# 20190608_ORIGAMI_V2-H-08slot-fixed.net
KiCad netlist of a schematic drawn in EAGLE
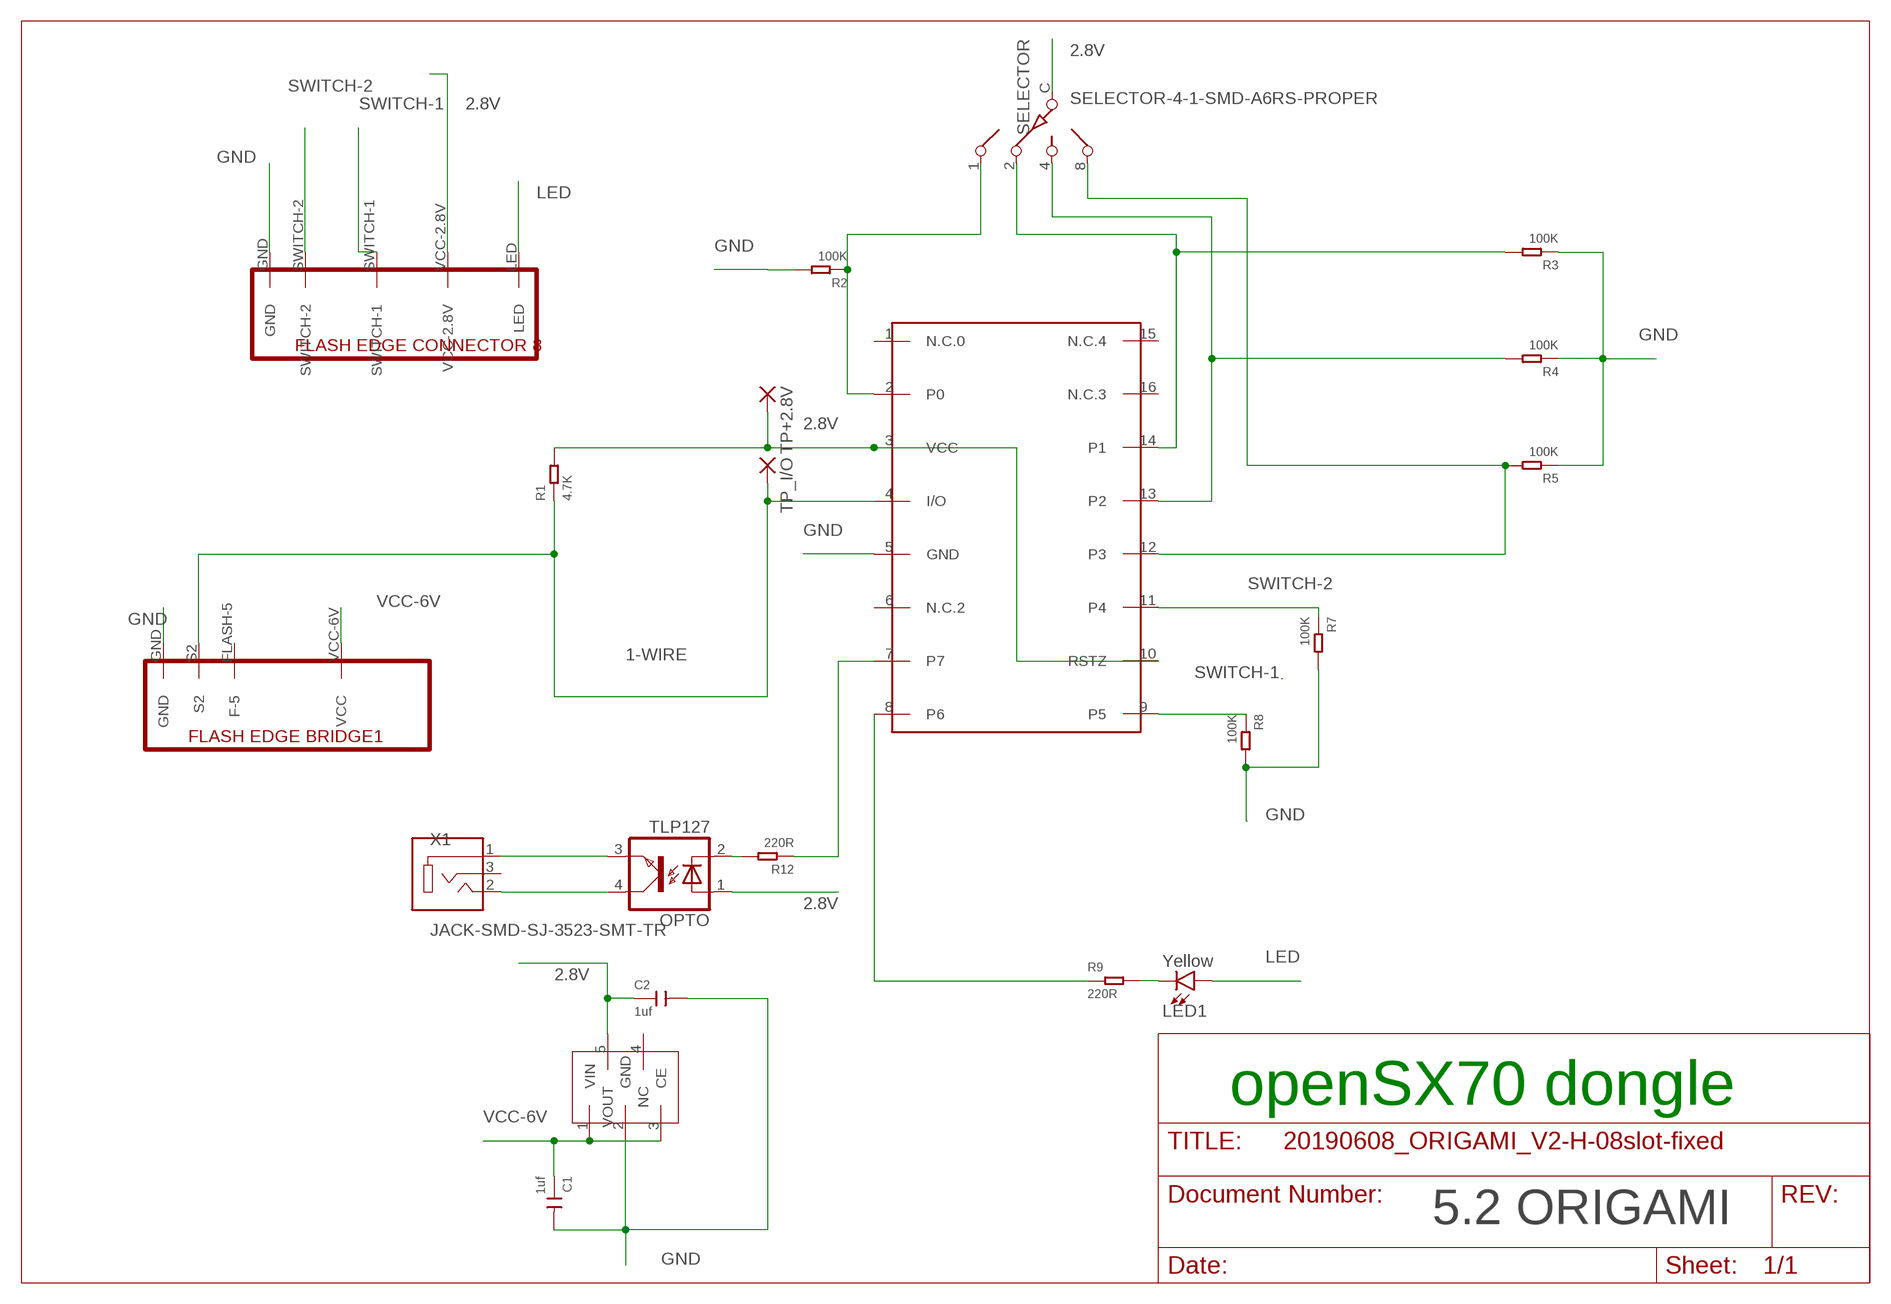
[diagram p0: schematic, sheet 1]

(export (version "E")
  (design (tool "Eeschema 10.0.6"))
  (components
    (comp (ref "C1")
      (value "1uf")
      (footprint "eagle-import:C0603")
      (fields (field (name "MPN") "CC0603KRX7R8BB105"))
      (libsource (lib "eagle-import") (part "CERAMIC-1UF-25V-10%-X7R(0603)"))
    )
    (comp (ref "C2")
      (value "1uf")
      (footprint "eagle-import:C0603")
      (fields (field (name "MPN") "CC0603KRX7R8BB105"))
      (libsource (lib "eagle-import") (part "CERAMIC-1UF-25V-10%-X7R(0603)"))
    )
    (comp (ref "DS2408")
      (value "DS2408")
      (footprint "eagle-import:SO16")
      (libsource (lib "eagle-import") (part "DS2408"))
    )
    (comp (ref "LED1")
      (value "Yellow")
      (footprint "eagle-import:LED-1206")
      (libsource (lib "eagle-import") (part "LED-YELLOWLILYPAD"))
    )
    (comp (ref "OPTO")
      (value "TLP127")
      (footprint "eagle-import:SO-4")
      (libsource (lib "eagle-import") (part "TLP127"))
    )
    (comp (ref "R1")
      (value "4.7K")
      (footprint "eagle-import:R0603")
      (fields (field (name "MPN") "RC0603JR-074K7L"))
      (libsource (lib "eagle-import") (part "SMD-RES-4.7K-5%-1/10W(0603)"))
    )
    (comp (ref "R2")
      (value "100K")
      (footprint "eagle-import:R0603")
      (fields (field (name "MPN") "RC0603FR-07100KL"))
      (libsource (lib "eagle-import") (part "SMD-RES-100K-1%-1/10W(0603)"))
    )
    (comp (ref "R3")
      (value "100K")
      (footprint "eagle-import:R0603")
      (fields (field (name "MPN") "RC0603FR-07100KL"))
      (libsource (lib "eagle-import") (part "SMD-RES-100K-1%-1/10W(0603)"))
    )
    (comp (ref "R4")
      (value "100K")
      (footprint "eagle-import:R0603")
      (fields (field (name "MPN") "RC0603FR-07100KL"))
      (libsource (lib "eagle-import") (part "SMD-RES-100K-1%-1/10W(0603)"))
    )
    (comp (ref "R5")
      (value "100K")
      (footprint "eagle-import:R0603")
      (fields (field (name "MPN") "RC0603FR-07100KL"))
      (libsource (lib "eagle-import") (part "SMD-RES-100K-1%-1/10W(0603)"))
    )
    (comp (ref "R7")
      (value "100K")
      (footprint "eagle-import:R0603")
      (fields (field (name "MPN") "RC0603FR-07100KL"))
      (libsource (lib "eagle-import") (part "SMD-RES-100K-1%-1/10W(0603)"))
    )
    (comp (ref "R8")
      (value "100K")
      (footprint "eagle-import:R0603")
      (fields (field (name "MPN") "RC0603FR-07100KL"))
      (libsource (lib "eagle-import") (part "SMD-RES-100K-1%-1/10W(0603)"))
    )
    (comp (ref "R9")
      (value "220R")
      (footprint "eagle-import:R0603")
      (fields (field (name "MPN") "RC0603JR-07220RL"))
      (libsource (lib "eagle-import") (part "SMD-RES-220R-5%-1/10W(0603)"))
    )
    (comp (ref "R12")
      (value "220R")
      (footprint "eagle-import:R0603")
      (fields (field (name "MPN") "RC0603JR-07220RL"))
      (libsource (lib "eagle-import") (part "SMD-RES-220R-5%-1/10W(0603)"))
    )
    (comp (ref "REG")
      (value "NCP4688")
      (footprint "eagle-import:SOT-23-5")
      (libsource (lib "eagle-import") (part "NCP4688"))
    )
    (comp (ref "SELECTOR")
      (value "SELECTOR-4-1-SMD-A6RS-PROPER")
      (footprint "eagle-import:A6RS-161RS")
      (libsource (lib "eagle-import") (part "SELECTOR-4-1-SMD-A6RS-PROPER"))
    )
    (comp (ref "TP+2.8V")
      (value "SMD2")
      (footprint "eagle-import:SMD1,27-2,54")
      (libsource (lib "eagle-import") (part "SMD2"))
    )
    (comp (ref "TP_I/O")
      (value "SMD2")
      (footprint "eagle-import:SMD1,27-2,54")
      (libsource (lib "eagle-import") (part "SMD2"))
    )
    (comp (ref "U$1")
      (value "FLASH-BRIDGE-SW1-SW2-LED")
      (footprint "eagle-import:FLASH-8-BRIDGE-SW1-SW2-LED")
      (libsource (lib "eagle-import") (part "FLASH-BRIDGE-SW1-SW2-LED"))
    )
    (comp (ref "U$2")
      (value "FLASH-BRIDGE1")
      (footprint "eagle-import:FLASH-8-BRIDGE1")
      (libsource (lib "eagle-import") (part "FLASH-BRIDGE1"))
    )
    (comp (ref "X1")
      (value "JACK-SMD-SJ-3523-SMT-TR")
      (footprint "eagle-import:CUI_SJ-3523-SMT-TR")
      (fields (field (name "MF") "CUI Inc.") (field (name "MP") "SJ-3523-SMT-TR"))
      (libsource (lib "eagle-import") (part "JACK-SMD-SJ-3523-SMT-TR"))
    )
  )
  (nets
    (net (code "1") (name "/1-WIRE") (class "Default")
      (node (ref "DS2408") (pin "4") (pinfunction "I/O_4") (pintype "bidirectional"))
      (node (ref "R1") (pin "1") (pinfunction "1_1") (pintype "passive"))
      (node (ref "TP_I/O") (pin "1") (pinfunction "P_1") (pintype "passive"))
      (node (ref "U$2") (pin "S2") (pinfunction "S2_S2") (pintype "bidirectional"))
    )
    (net (code "2") (name "/2.8V") (class "Default")
      (node (ref "C2") (pin "1") (pinfunction "1_1") (pintype "passive"))
      (node (ref "DS2408") (pin "10") (pinfunction "RSTZ_10") (pintype "bidirectional"))
      (node (ref "DS2408") (pin "3") (pinfunction "VCC_3") (pintype "bidirectional"))
      (node (ref "OPTO") (pin "1") (pinfunction "A_1") (pintype "passive"))
      (node (ref "R1") (pin "2") (pinfunction "2_2") (pintype "passive"))
      (node (ref "REG") (pin "5") (pinfunction "VOUT_5") (pintype "bidirectional"))
      (node (ref "SELECTOR") (pin "C") (pinfunction "C_C") (pintype "passive"))
      (node (ref "TP+2.8V") (pin "1") (pinfunction "P_1") (pintype "passive"))
      (node (ref "U$1") (pin "VCC-2.8V") (pinfunction "VCC-2.8V_VCC-2.8V") (pintype "bidirectional"))
    )
    (net (code "3") (name "/GND") (class "Default")
      (node (ref "C1") (pin "2") (pinfunction "2_2") (pintype "passive"))
      (node (ref "C2") (pin "2") (pinfunction "2_2") (pintype "passive"))
      (node (ref "DS2408") (pin "5") (pinfunction "GND_5") (pintype "bidirectional"))
      (node (ref "R2") (pin "2") (pinfunction "2_2") (pintype "passive"))
      (node (ref "R3") (pin "1") (pinfunction "1_1") (pintype "passive"))
      (node (ref "R4") (pin "1") (pinfunction "1_1") (pintype "passive"))
      (node (ref "R5") (pin "1") (pinfunction "1_1") (pintype "passive"))
      (node (ref "R7") (pin "2") (pinfunction "2_2") (pintype "passive"))
      (node (ref "R8") (pin "2") (pinfunction "2_2") (pintype "passive"))
      (node (ref "REG") (pin "2") (pinfunction "GND_2") (pintype "bidirectional"))
      (node (ref "U$1") (pin "GND") (pinfunction "GND_GND") (pintype "bidirectional"))
      (node (ref "U$2") (pin "GND") (pinfunction "GND_GND") (pintype "bidirectional"))
    )
    (net (code "4") (name "/LED") (class "Default")
      (node (ref "LED1") (pin "A") (pinfunction "A_A") (pintype "passive"))
      (node (ref "U$1") (pin "LED") (pinfunction "LED_LED") (pintype "bidirectional"))
    )
    (net (code "5") (name "/SWITCH-1") (class "Default")
      (node (ref "DS2408") (pin "9") (pinfunction "P5_9") (pintype "bidirectional"))
      (node (ref "R8") (pin "1") (pinfunction "1_1") (pintype "passive"))
      (node (ref "U$1") (pin "SWITCH-1") (pinfunction "SWITCH-1_SWITCH-1") (pintype "bidirectional"))
    )
    (net (code "6") (name "/SWITCH-2") (class "Default")
      (node (ref "DS2408") (pin "11") (pinfunction "P4_11") (pintype "bidirectional"))
      (node (ref "R7") (pin "1") (pinfunction "1_1") (pintype "passive"))
      (node (ref "U$1") (pin "SWITCH-2") (pinfunction "SWITCH-2_SWITCH-2") (pintype "bidirectional"))
    )
    (net (code "7") (name "/VCC-6V") (class "Default")
      (node (ref "C1") (pin "1") (pinfunction "1_1") (pintype "passive"))
      (node (ref "REG") (pin "1") (pinfunction "VIN_1") (pintype "bidirectional"))
      (node (ref "REG") (pin "3") (pinfunction "CE_3") (pintype "bidirectional"))
      (node (ref "U$2") (pin "VCC-6V") (pinfunction "VCC_VCC-6V") (pintype "bidirectional"))
    )
    (net (code "8") (name "Net-(DS2408-P0)") (class "Default")
      (node (ref "DS2408") (pin "2") (pinfunction "P0_2") (pintype "bidirectional"))
      (node (ref "R2") (pin "1") (pinfunction "1_1") (pintype "passive"))
      (node (ref "SELECTOR") (pin "1") (pinfunction "8_1") (pintype "passive"))
    )
    (net (code "9") (name "Net-(DS2408-P1)") (class "Default")
      (node (ref "DS2408") (pin "14") (pinfunction "P1_14") (pintype "bidirectional"))
      (node (ref "R3") (pin "2") (pinfunction "2_2") (pintype "passive"))
      (node (ref "SELECTOR") (pin "2") (pinfunction "4_2") (pintype "passive"))
    )
    (net (code "10") (name "Net-(DS2408-P2)") (class "Default")
      (node (ref "DS2408") (pin "13") (pinfunction "P2_13") (pintype "bidirectional"))
      (node (ref "R4") (pin "2") (pinfunction "2_2") (pintype "passive"))
      (node (ref "SELECTOR") (pin "4") (pinfunction "2_4") (pintype "passive"))
    )
    (net (code "11") (name "Net-(DS2408-P3)") (class "Default")
      (node (ref "DS2408") (pin "12") (pinfunction "P3_12") (pintype "bidirectional"))
      (node (ref "R5") (pin "2") (pinfunction "2_2") (pintype "passive"))
      (node (ref "SELECTOR") (pin "8") (pinfunction "1_8") (pintype "passive"))
    )
    (net (code "12") (name "Net-(DS2408-P6)") (class "Default")
      (node (ref "DS2408") (pin "8") (pinfunction "P6_8") (pintype "bidirectional"))
      (node (ref "R9") (pin "1") (pinfunction "1_1") (pintype "passive"))
    )
    (net (code "13") (name "Net-(DS2408-P7)") (class "Default")
      (node (ref "DS2408") (pin "7") (pinfunction "P7_7") (pintype "bidirectional"))
      (node (ref "R12") (pin "1") (pinfunction "1_1") (pintype "passive"))
    )
    (net (code "14") (name "Net-(LED1-PadC)") (class "Default")
      (node (ref "LED1") (pin "C") (pinfunction "C_C") (pintype "passive"))
      (node (ref "R9") (pin "2") (pinfunction "2_2") (pintype "passive"))
    )
    (net (code "15") (name "Net-(OPTO-C)") (class "Default")
      (node (ref "OPTO") (pin "2") (pinfunction "C_2") (pintype "passive"))
      (node (ref "R12") (pin "2") (pinfunction "2_2") (pintype "passive"))
    )
    (net (code "16") (name "Net-(OPTO-COL)") (class "Default")
      (node (ref "OPTO") (pin "4") (pinfunction "COL_4") (pintype "passive"))
      (node (ref "X1") (pin "2") (pinfunction "2_2") (pintype "passive"))
    )
    (net (code "17") (name "Net-(OPTO-EMIT)") (class "Default")
      (node (ref "OPTO") (pin "3") (pinfunction "EMIT_3") (pintype "passive"))
      (node (ref "X1") (pin "1") (pinfunction "1_1") (pintype "passive"))
    )
    (net (code "18") (name "unconnected-(DS2408-N.C.0-Pad1)") (class "Default")
      (node (ref "DS2408") (pin "1") (pinfunction "N.C.0_1") (pintype "bidirectional"))
    )
    (net (code "19") (name "unconnected-(DS2408-N.C.2-Pad6)") (class "Default")
      (node (ref "DS2408") (pin "6") (pinfunction "N.C.2_6") (pintype "bidirectional"))
    )
    (net (code "20") (name "unconnected-(DS2408-N.C.3-Pad16)") (class "Default")
      (node (ref "DS2408") (pin "16") (pinfunction "N.C.3_16") (pintype "bidirectional"))
    )
    (net (code "21") (name "unconnected-(DS2408-N.C.4-Pad15)") (class "Default")
      (node (ref "DS2408") (pin "15") (pinfunction "N.C.4_15") (pintype "bidirectional"))
    )
    (net (code "22") (name "unconnected-(REG-NC-Pad4)") (class "Default")
      (node (ref "REG") (pin "4") (pinfunction "NC_4") (pintype "bidirectional"))
    )
    (net (code "23") (name "unconnected-(U$2-F-5-PadFLASH-5)") (class "Default")
      (node (ref "U$2") (pin "FLASH-5") (pinfunction "F-5_FLASH-5") (pintype "bidirectional"))
    )
    (net (code "24") (name "unconnected-(X1-Pad3)") (class "Default")
      (node (ref "X1") (pin "3") (pinfunction "3_3") (pintype "passive"))
    )
  )
)
